# CCE_Simonduino_01.net
KiCad netlist of a schematic drawn in Altium Designer
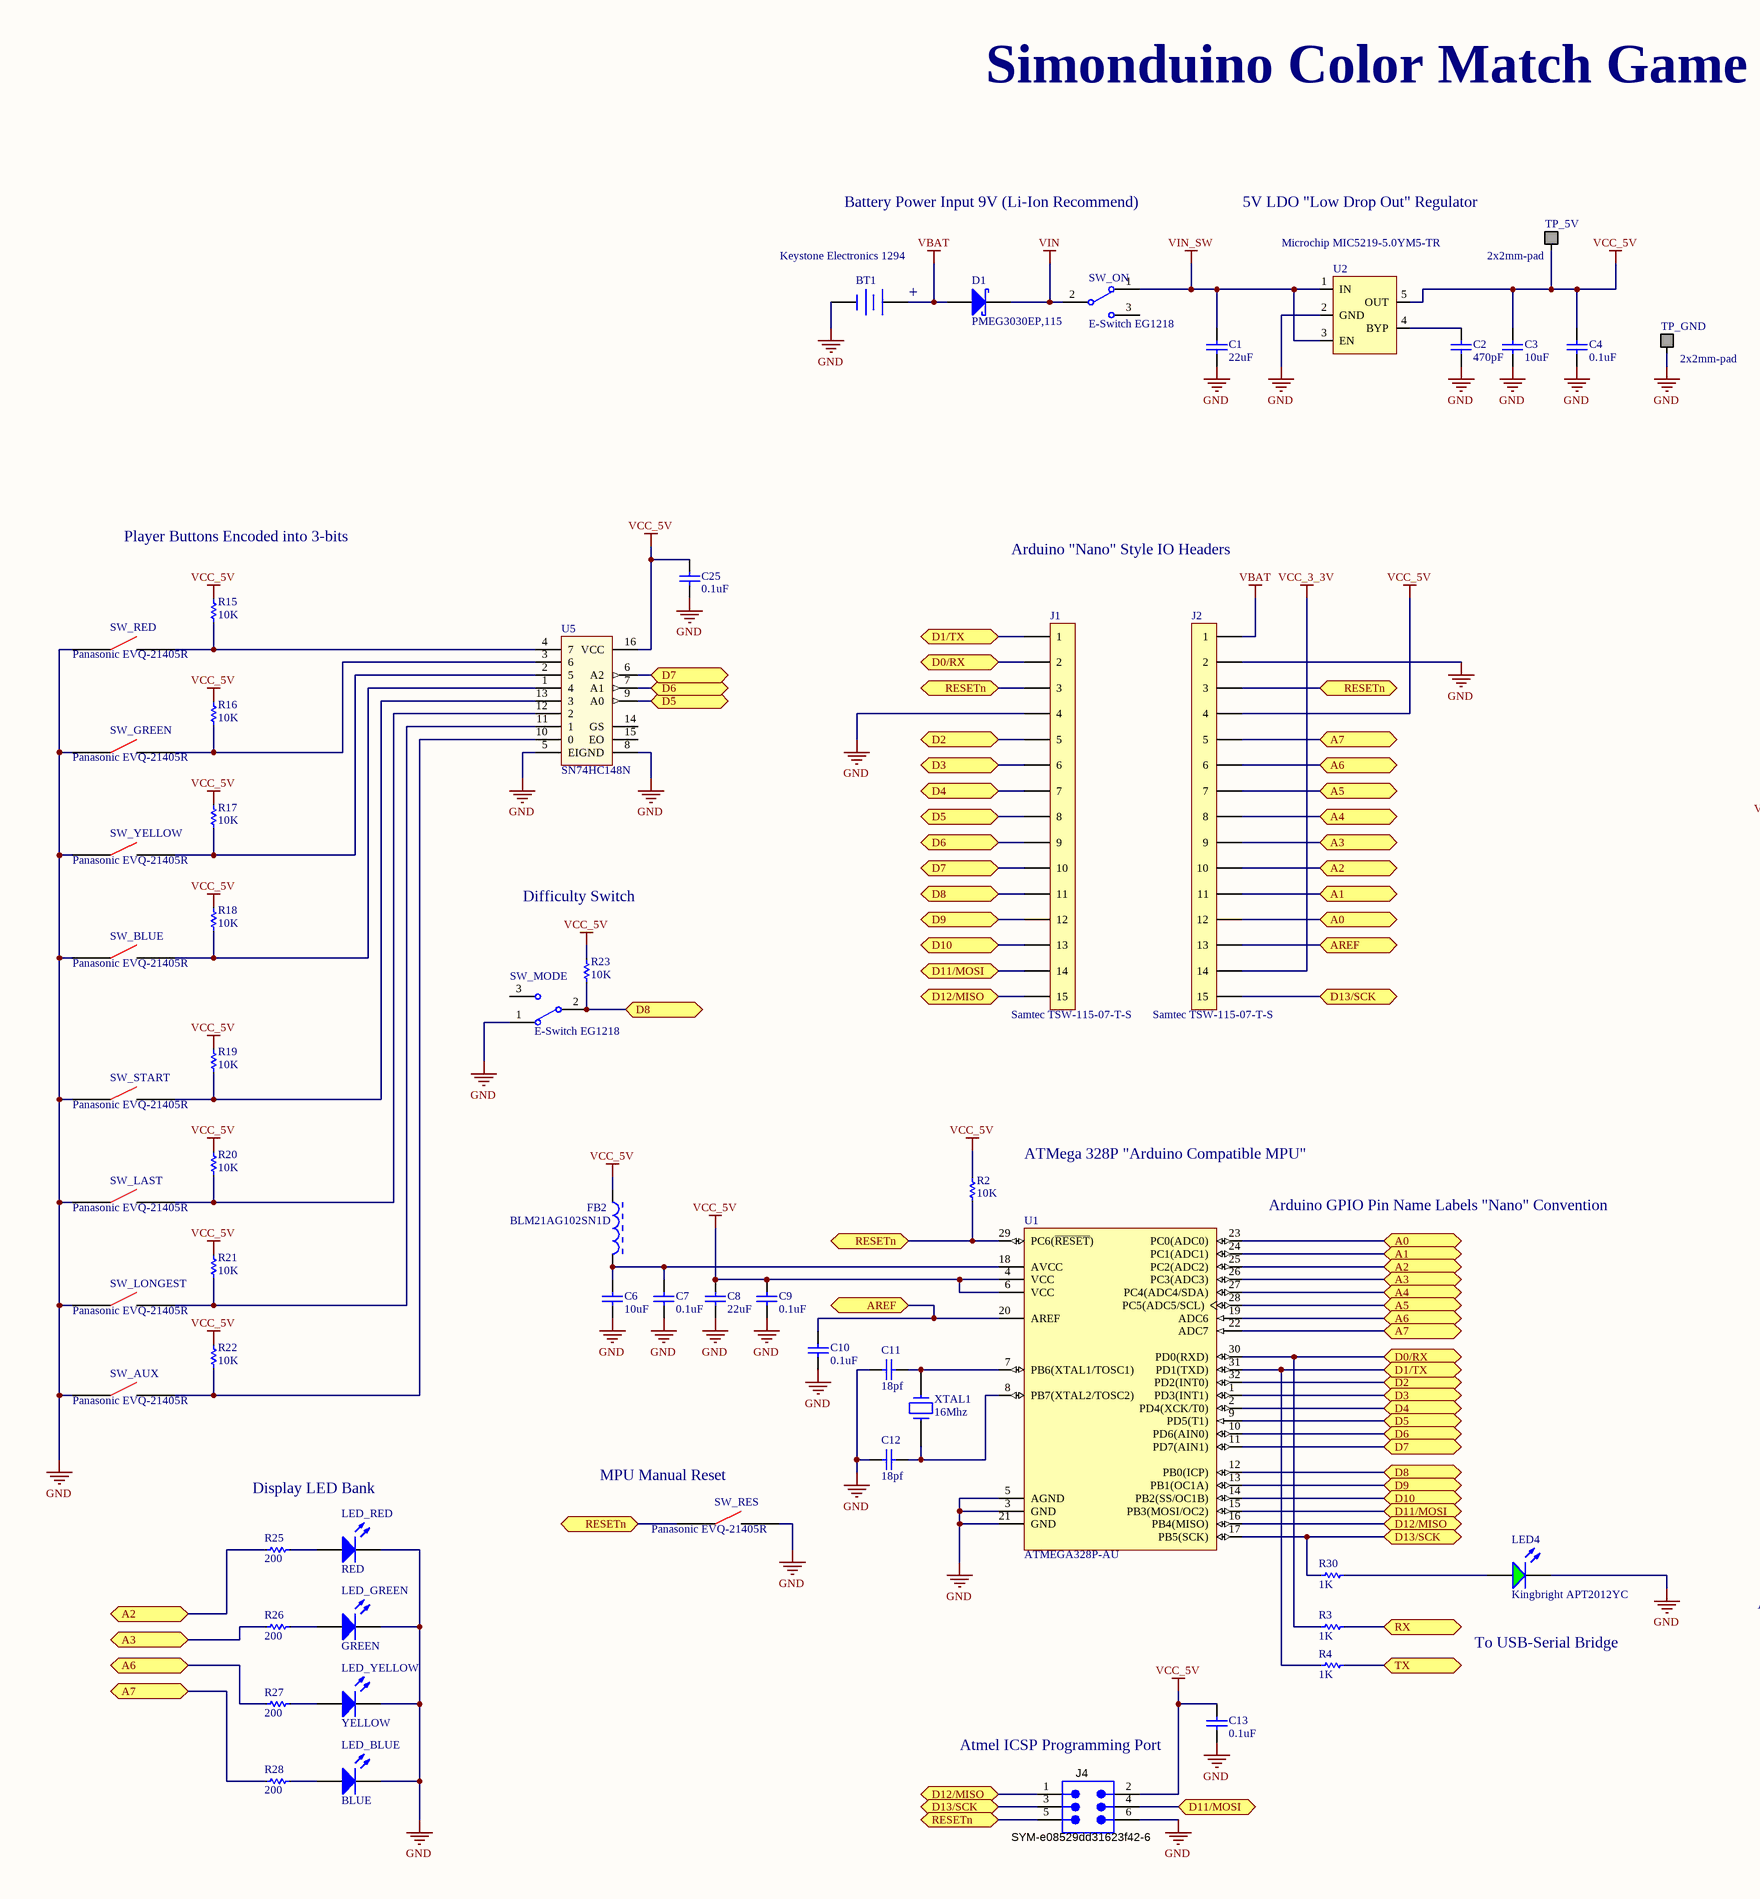
[diagram p0: CCE_Simonduino_01.SchDoc, left]
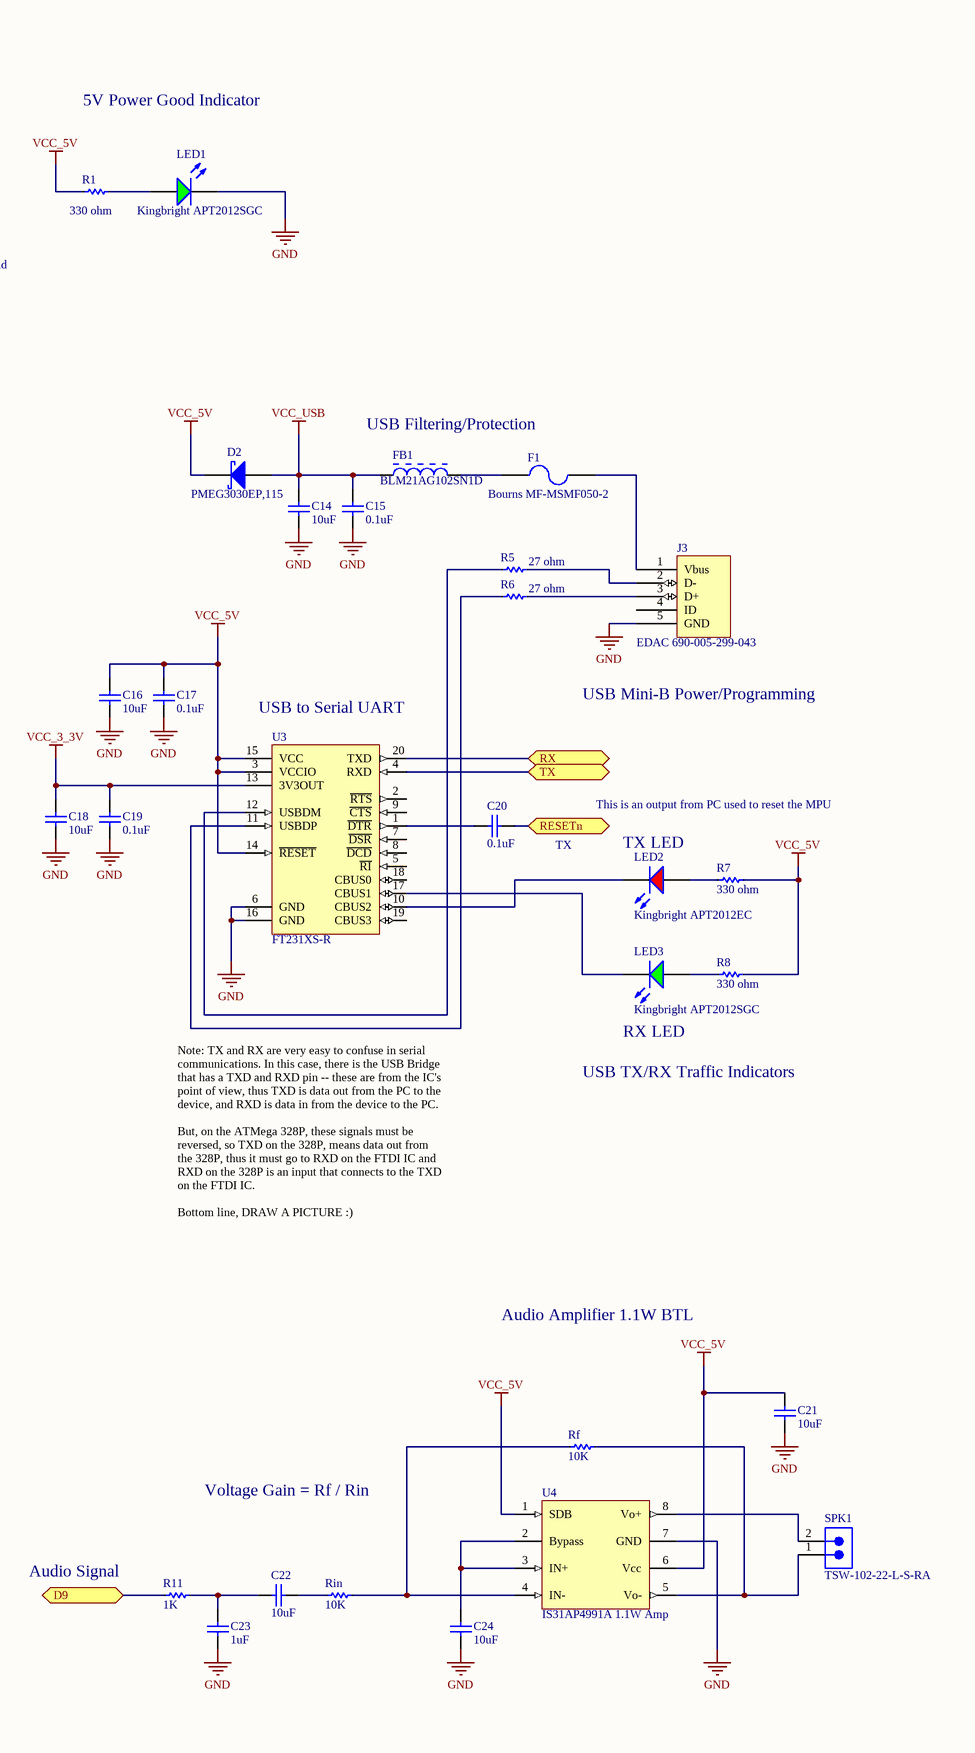
[diagram p1: CCE_Simonduino_01.SchDoc, right]

(export (version "E")
  (design (tool "Eeschema 10.0.6"))
  (components
    (comp (ref "BT1")
      (value "Keystone Electronics 1294")
      (footprint "PCB-3798-1")
      (description "HOLDER BATT 9V UNIV PLASTIC PC")
      (libsource (lib "Octopart library") (part "SYM-3798-1"))
    )
    (comp (ref "C1")
      (value "22uF")
      (footprint "RLP133A")
      (description "Generic Multilayer Ceramic Capacitor SMD 0805 (2012)")
      (libsource (lib "Octopart library") (part "SYM-3c98f6df3913e35f-5"))
    )
    (comp (ref "C2")
      (value "470pF")
      (footprint "RLP133A")
      (description "Generic Multilayer Ceramic Capacitor SMD 0805 (2012)")
      (libsource (lib "CommunityVault") (part "SYM-3c98f6df3913e35f-5"))
    )
    (comp (ref "C3")
      (value "10uF")
      (footprint "RLP133A")
      (description "Generic Multilayer Ceramic Capacitor SMD 0805 (2012)")
      (libsource (lib "Octopart library") (part "SYM-3c98f6df3913e35f-5"))
    )
    (comp (ref "C4")
      (value "0.1uF")
      (footprint "RLP133A")
      (description "Generic Multilayer Ceramic Capacitor SMD 0805 (2012)")
      (libsource (lib "Octopart library") (part "SYM-3c98f6df3913e35f-5"))
    )
    (comp (ref "C6")
      (value "10uF")
      (footprint "RLP133A")
      (description "Generic Multilayer Ceramic Capacitor SMD 0805 (2012)")
      (libsource (lib "Octopart library") (part "SYM-3c98f6df3913e35f-5"))
    )
    (comp (ref "C7")
      (value "0.1uF")
      (footprint "RLP133A")
      (description "Generic Multilayer Ceramic Capacitor SMD 0805 (2012)")
      (libsource (lib "Octopart library") (part "SYM-3c98f6df3913e35f-5"))
    )
    (comp (ref "C8")
      (value "22uF")
      (footprint "RLP133A")
      (description "Generic Multilayer Ceramic Capacitor SMD 0805 (2012)")
      (libsource (lib "Octopart library") (part "SYM-3c98f6df3913e35f-5"))
    )
    (comp (ref "C9")
      (value "0.1uF")
      (footprint "RLP133A")
      (description "Generic Multilayer Ceramic Capacitor SMD 0805 (2012)")
      (libsource (lib "Octopart library") (part "SYM-3c98f6df3913e35f-5"))
    )
    (comp (ref "C10")
      (value "0.1uF")
      (footprint "RLP133A")
      (description "Generic Multilayer Ceramic Capacitor SMD 0805 (2012)")
      (libsource (lib "Octopart library") (part "SYM-3c98f6df3913e35f-5"))
    )
    (comp (ref "C11")
      (value "18pf")
      (footprint "RLP133A")
      (description "Generic Multilayer Ceramic Capacitor SMD 0805 (2012)")
      (libsource (lib "Octopart library") (part "SYM-3c98f6df3913e35f-5"))
    )
    (comp (ref "C12")
      (value "18pf")
      (footprint "RLP133A")
      (description "Generic Multilayer Ceramic Capacitor SMD 0805 (2012)")
      (libsource (lib "Octopart library") (part "SYM-3c98f6df3913e35f-5"))
    )
    (comp (ref "C13")
      (value "0.1uF")
      (footprint "RLP133A")
      (description "Generic Multilayer Ceramic Capacitor SMD 0805 (2012)")
      (libsource (lib "Octopart library") (part "SYM-3c98f6df3913e35f-5"))
    )
    (comp (ref "C14")
      (value "10uF")
      (footprint "RLP133A")
      (description "Generic Multilayer Ceramic Capacitor SMD 0805 (2012)")
      (libsource (lib "Octopart library") (part "SYM-3c98f6df3913e35f-5"))
    )
    (comp (ref "C15")
      (value "0.1uF")
      (footprint "RLP133A")
      (description "Generic Multilayer Ceramic Capacitor SMD 0805 (2012)")
      (libsource (lib "Octopart library") (part "SYM-3c98f6df3913e35f-5"))
    )
    (comp (ref "C16")
      (value "10uF")
      (footprint "RLP133A")
      (description "Generic Multilayer Ceramic Capacitor SMD 0805 (2012)")
      (libsource (lib "Octopart library") (part "SYM-3c98f6df3913e35f-5"))
    )
    (comp (ref "C17")
      (value "0.1uF")
      (footprint "RLP133A")
      (description "Generic Multilayer Ceramic Capacitor SMD 0805 (2012)")
      (libsource (lib "Octopart library") (part "SYM-3c98f6df3913e35f-5"))
    )
    (comp (ref "C18")
      (value "10uF")
      (footprint "RLP133A")
      (description "Generic Multilayer Ceramic Capacitor SMD 0805 (2012)")
      (libsource (lib "Octopart library") (part "SYM-3c98f6df3913e35f-5"))
    )
    (comp (ref "C19")
      (value "0.1uF")
      (footprint "RLP133A")
      (description "Generic Multilayer Ceramic Capacitor SMD 0805 (2012)")
      (libsource (lib "Octopart library") (part "SYM-3c98f6df3913e35f-5"))
    )
    (comp (ref "C20")
      (value "0.1uF")
      (footprint "RLP133A")
      (description "Generic Multilayer Ceramic Capacitor SMD 0805 (2012)")
      (libsource (lib "Octopart library") (part "SYM-3c98f6df3913e35f-5"))
    )
    (comp (ref "C21")
      (value "10uF")
      (footprint "RLP133A")
      (description "Generic Multilayer Ceramic Capacitor SMD 0805 (2012)")
      (libsource (lib "Octopart library") (part "SYM-3c98f6df3913e35f-5"))
    )
    (comp (ref "C22")
      (value "10uF")
      (footprint "RLP133A")
      (description "Generic Multilayer Ceramic Capacitor SMD 0805 (2012)")
      (libsource (lib "Octopart library") (part "SYM-3c98f6df3913e35f-5"))
    )
    (comp (ref "C23")
      (value "1uF")
      (footprint "RLP133A")
      (description "Generic Multilayer Ceramic Capacitor SMD 0805 (2012)")
      (libsource (lib "Octopart library") (part "SYM-3c98f6df3913e35f-5"))
    )
    (comp (ref "C24")
      (value "10uF")
      (footprint "RLP133A")
      (description "Generic Multilayer Ceramic Capacitor SMD 0805 (2012)")
      (libsource (lib "Octopart library") (part "SYM-3c98f6df3913e35f-5"))
    )
    (comp (ref "C25")
      (value "0.1uF")
      (footprint "RLP133A")
      (description "Generic Multilayer Ceramic Capacitor SMD 0805 (2012)")
      (libsource (lib "Octopart library") (part "SYM-3c98f6df3913e35f-5"))
    )
    (comp (ref "D1")
      (value "PMEG3030EP,115")
      (footprint "PCB-ylvpw7uho1dkst7hexks-1")
      (description "PMEG3030EP 3 A 30 Vrrm SMT MEGA Schottky Barrier Rectifier - SOD-128F")
      (libsource (lib "Octopart library") (part "SYM-93505b4aaf424c97-1"))
    )
    (comp (ref "D2")
      (value "PMEG3030EP,115")
      (footprint "PCB-ylvpw7uho1dkst7hexks-1")
      (description "PMEG3030EP 3 A 30 Vrrm SMT MEGA Schottky Barrier Rectifier - SOD-128F")
      (libsource (lib "Octopart library") (part "SYM-93505b4aaf424c97-1"))
    )
    (comp (ref "F1")
      (value "Bourns MF-MSMF050-2")
      (footprint "L1812")
      (description "PTC RESETTABLE .50A 15V 1812")
      (libsource (lib "Octopart library") (part "BOUR-MF-MSMF050-2"))
    )
    (comp (ref "FB1")
      (value "BLM21AG102SN1D")
      (footprint "MURA-BLM21-H1-CHIP-2_V")
      (libsource (lib "Octopart library") (part "MURA-FB-2"))
    )
    (comp (ref "FB2")
      (value "BLM21AG102SN1D")
      (footprint "MURA-BLM21-H1-CHIP-2_V")
      (libsource (lib "Octopart library") (part "MURA-FB-2"))
    )
    (comp (ref "J1")
      (value "Samtec TSW-115-07-T-S")
      (footprint "PCB-ss9uik38su1ryg1jck95-1")
      (description "Conn Unshrouded Header HDR 15 POS 2.54mm Solder ST Thru-Hole Automotive Bulk")
      (libsource (lib "") (part "SYM-3393fa9d3e8bec54-1_1"))
    )
    (comp (ref "J2")
      (value "Samtec TSW-115-07-T-S")
      (footprint "PCB-ss9uik38su1ryg1jck95-1")
      (description "Conn Unshrouded Header HDR 15 POS 2.54mm Solder ST Thru-Hole Automotive Bulk")
      (libsource (lib "Octopart library") (part "SYM-3393fa9d3e8bec54-1"))
    )
    (comp (ref "J3")
      (value "EDAC 690-005-299-043")
      (footprint "PCB-0dqtvzwtjwndkeioqta0-1")
      (description "5 Pin Right Angle Surface Mount Mini USB Type B")
      (libsource (lib "CommunityVault") (part "SYM-f10139da97e32ec6-1"))
    )
    (comp (ref "J4")
      (value "SYM-e08529dd31623f42-6")
      (footprint "PCB-2h1t0rpz2tx2wsc79kkt-1")
      (description "2.54mm (0.1\") Pitch DIL Vertical PC Tail Pin Header, 6.1mm mating pin height, tin, 3+3 contacts")
      (fields (field (name "MANUFACTURER PART NUMBER") "M20-9980346"))
      (libsource (lib "Octopart library") (part "SYM-e08529dd31623f42-6"))
    )
    (comp (ref "LED1")
      (value "Kingbright APT2012SGC")
      (footprint "CHIPLED_0805_NOOUTLINE")
      (description "LED 2X1.2MM 568NM GN WTR CLR SMD")
      (libsource (lib "Octopart library") (part "LED_GREEN_AC"))
    )
    (comp (ref "LED2")
      (value "Kingbright APT2012EC")
      (footprint "CHIPLED_0805_NOOUTLINE")
      (description "LED 2X1.2MM 625NM RD WTR CLR SMD")
      (libsource (lib "Octopart library") (part "LED_RED_AC"))
    )
    (comp (ref "LED3")
      (value "Kingbright APT2012SGC")
      (footprint "CHIPLED_0805_NOOUTLINE")
      (description "LED 2X1.2MM 568NM GN WTR CLR SMD")
      (libsource (lib "Octopart library") (part "LED_GREEN_AC"))
    )
    (comp (ref "LED4")
      (value "Kingbright APT2012YC")
      (footprint "CHIPLED_0805_NOOUTLINE")
      (description "LED 2X1.2MM 568NM GN WTR CLR SMD")
      (libsource (lib "CommunityVault") (part "CMP-1546221-2"))
    )
    (comp (ref "LED_BLUE")
      (value "BLUE")
      (footprint "PCB-teu6t62n2bsx7jl1if62-1")
      (description "LED Uni-Color Green 2-Pin T-1 3/4 Bulk")
      (fields
        (field (name "MANUFACTURER PART NUMBER") "C503B-GCN-CY0C0791")
        (field (name "MANUFACTURER") "Cree")
      )
      (libsource (lib "FavoritesLibrary") (part "SYM-92bb5b2eff764d7c-1"))
    )
    (comp (ref "LED_GREEN")
      (value "GREEN")
      (footprint "PCB-teu6t62n2bsx7jl1if62-1")
      (description "LED Uni-Color Green 2-Pin T-1 3/4 Bulk")
      (fields
        (field (name "MANUFACTURER PART NUMBER") "C503B-GCN-CY0C0791")
        (field (name "MANUFACTURER") "Cree")
      )
      (libsource (lib "FavoritesLibrary") (part "SYM-92bb5b2eff764d7c-1"))
    )
    (comp (ref "LED_RED")
      (value "RED")
      (footprint "PCB-teu6t62n2bsx7jl1if62-1")
      (description "LED Uni-Color Green 2-Pin T-1 3/4 Bulk")
      (fields
        (field (name "MANUFACTURER PART NUMBER") "C503B-GCN-CY0C0791")
        (field (name "MANUFACTURER") "Cree")
      )
      (libsource (lib "FavoritesLibrary") (part "SYM-92bb5b2eff764d7c-1"))
    )
    (comp (ref "LED_YELLOW")
      (value "YELLOW")
      (footprint "PCB-teu6t62n2bsx7jl1if62-1")
      (description "LED Uni-Color Green 2-Pin T-1 3/4 Bulk")
      (fields
        (field (name "MANUFACTURER PART NUMBER") "C503B-GCN-CY0C0791")
        (field (name "MANUFACTURER") "Cree")
      )
      (libsource (lib "FavoritesLibrary") (part "SYM-92bb5b2eff764d7c-1"))
    )
    (comp (ref "R1")
      (value "330 ohm")
      (footprint "RESC2013X70X40LL20T20")
      (description "@ RESISTOR,SMT,0805,1K OHM, +/-1%,+-100ppm,THICKFILM(100)")
      (libsource (lib "Octopart library") (part "RES-2"))
    )
    (comp (ref "R2")
      (value "10K")
      (footprint "RESC2013X70X40LL20T20")
      (description "@ RESISTOR,SMT,0805,1K OHM, +/-1%,+-100ppm,THICKFILM(100)")
      (libsource (lib "Octopart library") (part "RES-2"))
    )
    (comp (ref "R3")
      (value "1K")
      (footprint "RESC2013X70X40LL20T20")
      (description "@ RESISTOR,SMT,0805,1K OHM, +/-1%,+-100ppm,THICKFILM(100)")
      (libsource (lib "Octopart library") (part "RES-2"))
    )
    (comp (ref "R4")
      (value "1K")
      (footprint "RESC2013X70X40LL20T20")
      (description "@ RESISTOR,SMT,0805,1K OHM, +/-1%,+-100ppm,THICKFILM(100)")
      (libsource (lib "Octopart library") (part "RES-2"))
    )
    (comp (ref "R5")
      (value "27 ohm")
      (footprint "RESC2013X70X40LL20T20")
      (description "@ RESISTOR,SMT,0805,1K OHM, +/-1%,+-100ppm,THICKFILM(100)")
      (libsource (lib "Octopart library") (part "RES-2"))
    )
    (comp (ref "R6")
      (value "27 ohm")
      (footprint "RESC2013X70X40LL20T20")
      (description "@ RESISTOR,SMT,0805,1K OHM, +/-1%,+-100ppm,THICKFILM(100)")
      (libsource (lib "Octopart library") (part "RES-2"))
    )
    (comp (ref "R7")
      (value "330 ohm")
      (footprint "RESC2013X70X40LL20T20")
      (description "@ RESISTOR,SMT,0805,1K OHM, +/-1%,+-100ppm,THICKFILM(100)")
      (libsource (lib "Octopart library") (part "RES-2"))
    )
    (comp (ref "R8")
      (value "330 ohm")
      (footprint "RESC2013X70X40LL20T20")
      (description "@ RESISTOR,SMT,0805,1K OHM, +/-1%,+-100ppm,THICKFILM(100)")
      (libsource (lib "Octopart library") (part "RES-2"))
    )
    (comp (ref "R11")
      (value "1K")
      (footprint "RESC2013X70X40LL20T20")
      (description "@ RESISTOR,SMT,0805,1K OHM, +/-1%,+-100ppm,THICKFILM(100)")
      (libsource (lib "Octopart library") (part "RES-2"))
    )
    (comp (ref "R15")
      (value "10K")
      (footprint "RESC2013X70X40LL20T20")
      (description "@ RESISTOR,SMT,0805,1K OHM, +/-1%,+-100ppm,THICKFILM(100)")
      (libsource (lib "Octopart library") (part "RES-2"))
    )
    (comp (ref "R16")
      (value "10K")
      (footprint "RESC2013X70X40LL20T20")
      (description "@ RESISTOR,SMT,0805,1K OHM, +/-1%,+-100ppm,THICKFILM(100)")
      (libsource (lib "Octopart library") (part "RES-2"))
    )
    (comp (ref "R17")
      (value "10K")
      (footprint "RESC2013X70X40LL20T20")
      (description "@ RESISTOR,SMT,0805,1K OHM, +/-1%,+-100ppm,THICKFILM(100)")
      (libsource (lib "Octopart library") (part "RES-2"))
    )
    (comp (ref "R18")
      (value "10K")
      (footprint "RESC2013X70X40LL20T20")
      (description "@ RESISTOR,SMT,0805,1K OHM, +/-1%,+-100ppm,THICKFILM(100)")
      (libsource (lib "Octopart library") (part "RES-2"))
    )
    (comp (ref "R19")
      (value "10K")
      (footprint "RESC2013X70X40LL20T20")
      (description "@ RESISTOR,SMT,0805,1K OHM, +/-1%,+-100ppm,THICKFILM(100)")
      (libsource (lib "Octopart library") (part "RES-2"))
    )
    (comp (ref "R20")
      (value "10K")
      (footprint "RESC2013X70X40LL20T20")
      (description "@ RESISTOR,SMT,0805,1K OHM, +/-1%,+-100ppm,THICKFILM(100)")
      (libsource (lib "Octopart library") (part "RES-2"))
    )
    (comp (ref "R21")
      (value "10K")
      (footprint "RESC2013X70X40LL20T20")
      (description "@ RESISTOR,SMT,0805,1K OHM, +/-1%,+-100ppm,THICKFILM(100)")
      (libsource (lib "Octopart library") (part "RES-2"))
    )
    (comp (ref "R22")
      (value "10K")
      (footprint "RESC2013X70X40LL20T20")
      (description "@ RESISTOR,SMT,0805,1K OHM, +/-1%,+-100ppm,THICKFILM(100)")
      (libsource (lib "Octopart library") (part "RES-2"))
    )
    (comp (ref "R23")
      (value "10K")
      (footprint "RESC2013X70X40LL20T20")
      (description "@ RESISTOR,SMT,0805,1K OHM, +/-1%,+-100ppm,THICKFILM(100)")
      (libsource (lib "Octopart library") (part "RES-2"))
    )
    (comp (ref "R25")
      (value "200")
      (footprint "RESC2013X70X40LL20T20")
      (description "@ RESISTOR,SMT,0805,1K OHM, +/-1%,+-100ppm,THICKFILM(100)")
      (libsource (lib "Octopart library") (part "RES-2"))
    )
    (comp (ref "R26")
      (value "200")
      (footprint "RESC2013X70X40LL20T20")
      (description "@ RESISTOR,SMT,0805,1K OHM, +/-1%,+-100ppm,THICKFILM(100)")
      (libsource (lib "Octopart library") (part "RES-2"))
    )
    (comp (ref "R27")
      (value "200")
      (footprint "RESC2013X70X40LL20T20")
      (description "@ RESISTOR,SMT,0805,1K OHM, +/-1%,+-100ppm,THICKFILM(100)")
      (libsource (lib "Octopart library") (part "RES-2"))
    )
    (comp (ref "R28")
      (value "200")
      (footprint "RESC2013X70X40LL20T20")
      (description "@ RESISTOR,SMT,0805,1K OHM, +/-1%,+-100ppm,THICKFILM(100)")
      (libsource (lib "Octopart library") (part "RES-2"))
    )
    (comp (ref "R30")
      (value "1K")
      (footprint "RESC2013X70X40LL20T20")
      (description "@ RESISTOR,SMT,0805,1K OHM, +/-1%,+-100ppm,THICKFILM(100)")
      (libsource (lib "Octopart library") (part "RES-2"))
    )
    (comp (ref "Rf")
      (value "10K")
      (footprint "RESC2013X70X40LL20T20")
      (description "@ RESISTOR,SMT,0805,1K OHM, +/-1%,+-100ppm,THICKFILM(100)")
      (libsource (lib "Octopart library") (part "RES-2"))
    )
    (comp (ref "Rin")
      (value "10K")
      (footprint "RESC2013X70X40LL20T20")
      (description "@ RESISTOR,SMT,0805,1K OHM, +/-1%,+-100ppm,THICKFILM(100)")
      (libsource (lib "Octopart library") (part "RES-2"))
    )
    (comp (ref "SPK1")
      (value "TSW-102-22-L-S-RA")
      (footprint "SMTC-TSW-102-22-X-S-RA")
      (libsource (lib "Octopart library") (part "SMTC-TSW-102-X-X-S-X"))
    )
    (comp (ref "SW_AUX")
      (value "Panasonic EVQ-21405R")
      (footprint "PCB-je10m8m3eogq13l465bo-1")
      (description "Switch Tactile N.O. SPST Round Button PC Pins 0.02A 15VDC 1.3N Thru-Hole Radial T/R")
      (fields
        (field (name "ELEMENT14 PART NO.") "2281982")
        (field (name "MANUFACTURER PART NUMBER") "EVQ-21405R")
      )
      (libsource (lib "FavoritesLibrary") (part "SYM-2fe5e5be239cf022-1"))
    )
    (comp (ref "SW_BLUE")
      (value "Panasonic EVQ-21405R")
      (footprint "PCB-je10m8m3eogq13l465bo-1")
      (description "Switch Tactile N.O. SPST Round Button PC Pins 0.02A 15VDC 1.3N Thru-Hole Radial T/R")
      (fields
        (field (name "ELEMENT14 PART NO.") "2281982")
        (field (name "MANUFACTURER PART NUMBER") "EVQ-21405R")
      )
      (libsource (lib "FavoritesLibrary") (part "SYM-2fe5e5be239cf022-1"))
    )
    (comp (ref "SW_GREEN")
      (value "Panasonic EVQ-21405R")
      (footprint "PCB-je10m8m3eogq13l465bo-1")
      (description "Switch Tactile N.O. SPST Round Button PC Pins 0.02A 15VDC 1.3N Thru-Hole Radial T/R")
      (fields
        (field (name "ELEMENT14 PART NO.") "2281982")
        (field (name "MANUFACTURER PART NUMBER") "EVQ-21405R")
      )
      (libsource (lib "FavoritesLibrary") (part "SYM-2fe5e5be239cf022-1"))
    )
    (comp (ref "SW_LAST")
      (value "Panasonic EVQ-21405R")
      (footprint "PCB-je10m8m3eogq13l465bo-1")
      (description "Switch Tactile N.O. SPST Round Button PC Pins 0.02A 15VDC 1.3N Thru-Hole Radial T/R")
      (fields
        (field (name "ELEMENT14 PART NO.") "2281982")
        (field (name "MANUFACTURER PART NUMBER") "EVQ-21405R")
      )
      (libsource (lib "FavoritesLibrary") (part "SYM-2fe5e5be239cf022-1"))
    )
    (comp (ref "SW_LONGEST")
      (value "Panasonic EVQ-21405R")
      (footprint "PCB-je10m8m3eogq13l465bo-1")
      (description "Switch Tactile N.O. SPST Round Button PC Pins 0.02A 15VDC 1.3N Thru-Hole Radial T/R")
      (fields
        (field (name "ELEMENT14 PART NO.") "2281982")
        (field (name "MANUFACTURER PART NUMBER") "EVQ-21405R")
      )
      (libsource (lib "FavoritesLibrary") (part "SYM-2fe5e5be239cf022-1"))
    )
    (comp (ref "SW_MODE")
      (value "E-Switch EG1218")
      (footprint "ESWI-EG1218_V")
      (description "Slide Switch, 500 V, -20 to 70 degC, 3-Pin THD, RoHS")
      (fields (field (name "MANUFACTURER PART NUMBER") "EG1218"))
      (libsource (lib "FavoritesLibrary") (part "SW-SPDT-3_B"))
    )
    (comp (ref "SW_ON")
      (value "E-Switch EG1218")
      (footprint "ESWI-EG1218_V")
      (description "Slide Switch, 500 V, -20 to 70 degC, 3-Pin THD, RoHS")
      (fields (field (name "MANUFACTURER PART NUMBER") "EG1218"))
      (libsource (lib "FavoritesLibrary") (part "SW-SPDT-3_B"))
    )
    (comp (ref "SW_RED")
      (value "Panasonic EVQ-21405R")
      (footprint "PCB-je10m8m3eogq13l465bo-1")
      (description "Switch Tactile N.O. SPST Round Button PC Pins 0.02A 15VDC 1.3N Thru-Hole Radial T/R")
      (fields
        (field (name "ELEMENT14 PART NO.") "2281982")
        (field (name "MANUFACTURER PART NUMBER") "EVQ-21405R")
      )
      (libsource (lib "FavoritesLibrary") (part "SYM-2fe5e5be239cf022-1"))
    )
    (comp (ref "SW_RES")
      (value "Panasonic EVQ-21405R")
      (footprint "PCB-je10m8m3eogq13l465bo-1")
      (description "Switch Tactile N.O. SPST Round Button PC Pins 0.02A 15VDC 1.3N Thru-Hole Radial T/R")
      (fields
        (field (name "ELEMENT14 PART NO.") "2281982")
        (field (name "MANUFACTURER PART NUMBER") "EVQ-21405R")
      )
      (libsource (lib "FavoritesLibrary") (part "SYM-2fe5e5be239cf022-1"))
    )
    (comp (ref "SW_START")
      (value "Panasonic EVQ-21405R")
      (footprint "PCB-je10m8m3eogq13l465bo-1")
      (description "Switch Tactile N.O. SPST Round Button PC Pins 0.02A 15VDC 1.3N Thru-Hole Radial T/R")
      (fields
        (field (name "ELEMENT14 PART NO.") "2281982")
        (field (name "MANUFACTURER PART NUMBER") "EVQ-21405R")
      )
      (libsource (lib "FavoritesLibrary") (part "SYM-2fe5e5be239cf022-1"))
    )
    (comp (ref "SW_YELLOW")
      (value "Panasonic EVQ-21405R")
      (footprint "PCB-je10m8m3eogq13l465bo-1")
      (description "Switch Tactile N.O. SPST Round Button PC Pins 0.02A 15VDC 1.3N Thru-Hole Radial T/R")
      (fields
        (field (name "ELEMENT14 PART NO.") "2281982")
        (field (name "MANUFACTURER PART NUMBER") "EVQ-21405R")
      )
      (libsource (lib "FavoritesLibrary") (part "SYM-2fe5e5be239cf022-1"))
    )
    (comp (ref "TP_5V")
      (value "2x2mm-pad")
      (footprint "PCB-iek5qk9ganu4yn12lo6h-1")
      (description "Raychem; SMT Circuit probe pad, 0805, 0R0 RCT")
      (libsource (lib "Octopart library") (part "SYM-da21135b2be305e6-1"))
    )
    (comp (ref "TP_GND")
      (value "2x2mm-pad")
      (footprint "PCB-iek5qk9ganu4yn12lo6h-1")
      (description "Raychem; SMT Circuit probe pad, 0805, 0R0 RCT")
      (libsource (lib "Octopart library") (part "SYM-da21135b2be305e6-1"))
    )
    (comp (ref "U1")
      (value "ATMEGA328P-AU")
      (footprint "TQFP32-08")
      (libsource (lib "Octopart library") (part "ATMEGA328P-AU"))
    )
    (comp (ref "U2")
      (value "Microchip MIC5219-5.0YM5-TR")
      (footprint "PCB-wkjlo8hhy83bmub82728-1")
      (description "MIC5219 Series 500 mA 5 V Fixed Output Surface Mount LDO Regulator - SOT-23-5")
      (fields (field (name "MANUFACTURER PART NUMBER") "MIC5219-5.0YM5-TR"))
      (libsource (lib "CommunityVault") (part "SYM-8be04111fcdb5427-1"))
    )
    (comp (ref "U3")
      (value "FT231XS-R")
      (footprint "SSOP20_L")
      (description "USB Full Speed to Full Handshake UART with USB Charger Detection")
      (libsource (lib "Octopart library") (part "FTDI-FT231XS-20"))
    )
    (comp (ref "U4")
      (value "IS31AP4991A 1.1W Amp")
      (footprint "PCB-9rmbxp4o58shl47xlmib-1")
      (description "Audio Amp Speaker 1-CH Mono 1.4W Class-AB 8-Pin SOP T/R")
      (libsource (lib "Octopart library") (part "SYM-b3f478ed30436c33-1"))
    )
    (comp (ref "U5")
      (value "SN74HC148N")
      (footprint "PCB-humlfp2qb5uk19pmpc47-1")
      (description "8-Line To 3-Line Priority Encoders 16-SOIC -40 to 85")
      (libsource (lib "Octopart library") (part "SYM-21e6e8edbd0afe21-1"))
    )
    (comp (ref "XTAL1")
      (value "16Mhz")
      (footprint "PCB-tw4o7k9ciwtd4bkcirmp-1")
      (description "Crystal 16.0000 MHz")
      (fields (field (name "MANUFACTURER PART NUMBER") "9B-16.000MEEJ-B"))
      (libsource (lib "Octopart library") (part "SYM-9941515555464686-1"))
    )
  )
  (nets
    (net (code "1") (name "/A0") (class "Default")
      (node (ref "J2") (pin "12") (pinfunction "12_12") (pintype "passive"))
      (node (ref "U1") (pin "23") (pinfunction "PC0(ADC0)_23") (pintype "bidirectional"))
    )
    (net (code "2") (name "/A1") (class "Default")
      (node (ref "J2") (pin "11") (pinfunction "11_11") (pintype "passive"))
      (node (ref "U1") (pin "24") (pinfunction "PC1(ADC1)_24") (pintype "bidirectional"))
    )
    (net (code "3") (name "/A2") (class "Default")
      (node (ref "J2") (pin "10") (pinfunction "10_10") (pintype "passive"))
      (node (ref "R25") (pin "1") (pinfunction "1_1") (pintype "passive"))
      (node (ref "U1") (pin "25") (pinfunction "PC2(ADC2)_25") (pintype "bidirectional"))
    )
    (net (code "4") (name "/A3") (class "Default")
      (node (ref "J2") (pin "9") (pinfunction "9_9") (pintype "passive"))
      (node (ref "R26") (pin "1") (pinfunction "1_1") (pintype "passive"))
      (node (ref "U1") (pin "26") (pinfunction "PC3(ADC3)_26") (pintype "bidirectional"))
    )
    (net (code "5") (name "/A4") (class "Default")
      (node (ref "J2") (pin "8") (pinfunction "8_8") (pintype "passive"))
      (node (ref "U1") (pin "27") (pinfunction "PC4(ADC4/SDA)_27") (pintype "bidirectional"))
    )
    (net (code "6") (name "/A5") (class "Default")
      (node (ref "J2") (pin "7") (pinfunction "7_7") (pintype "passive"))
      (node (ref "U1") (pin "28") (pinfunction "PC5(ADC5/SCL)_28") (pintype "bidirectional"))
    )
    (net (code "7") (name "/A6") (class "Default")
      (node (ref "J2") (pin "6") (pinfunction "6_6") (pintype "passive"))
      (node (ref "R27") (pin "1") (pinfunction "1_1") (pintype "passive"))
      (node (ref "U1") (pin "19") (pinfunction "ADC6_19") (pintype "input"))
    )
    (net (code "8") (name "/A7") (class "Default")
      (node (ref "J2") (pin "5") (pinfunction "5_5") (pintype "passive"))
      (node (ref "R28") (pin "1") (pinfunction "1_1") (pintype "passive"))
      (node (ref "U1") (pin "22") (pinfunction "ADC7_22") (pintype "input"))
    )
    (net (code "9") (name "/AREF") (class "Default")
      (node (ref "C10") (pin "1") (pinfunction "1_1") (pintype "passive"))
      (node (ref "J2") (pin "13") (pinfunction "13_13") (pintype "passive"))
      (node (ref "U1") (pin "20") (pinfunction "AREF_20") (pintype "passive"))
    )
    (net (code "10") (name "/D0{slash}RX") (class "Default")
      (node (ref "J1") (pin "2") (pinfunction "2_2") (pintype "passive"))
      (node (ref "R3") (pin "1") (pinfunction "1_1") (pintype "passive"))
      (node (ref "U1") (pin "30") (pinfunction "PD0(RXD)_30") (pintype "bidirectional"))
    )
    (net (code "11") (name "/D1{slash}TX") (class "Default")
      (node (ref "J1") (pin "1") (pinfunction "1_1") (pintype "passive"))
      (node (ref "R4") (pin "1") (pinfunction "1_1") (pintype "passive"))
      (node (ref "U1") (pin "31") (pinfunction "PD1(TXD)_31") (pintype "bidirectional"))
    )
    (net (code "12") (name "/D2") (class "Default")
      (node (ref "J1") (pin "5") (pinfunction "5_5") (pintype "passive"))
      (node (ref "U1") (pin "32") (pinfunction "PD2(INT0)_32") (pintype "bidirectional"))
    )
    (net (code "13") (name "/D3") (class "Default")
      (node (ref "J1") (pin "6") (pinfunction "6_6") (pintype "passive"))
      (node (ref "U1") (pin "1") (pinfunction "PD3(INT1)_1") (pintype "bidirectional"))
    )
    (net (code "14") (name "/D4") (class "Default")
      (node (ref "J1") (pin "7") (pinfunction "7_7") (pintype "passive"))
      (node (ref "U1") (pin "2") (pinfunction "PD4(XCK/T0)_2") (pintype "bidirectional"))
    )
    (net (code "15") (name "/D5") (class "Default")
      (node (ref "J1") (pin "8") (pinfunction "8_8") (pintype "passive"))
      (node (ref "U1") (pin "9") (pinfunction "PD5(T1)_9") (pintype "input"))
      (node (ref "U5") (pin "9") (pinfunction "A0_9") (pintype "output"))
    )
    (net (code "16") (name "/D6") (class "Default")
      (node (ref "J1") (pin "9") (pinfunction "9_9") (pintype "passive"))
      (node (ref "U1") (pin "10") (pinfunction "PD6(AIN0)_10") (pintype "bidirectional"))
      (node (ref "U5") (pin "7") (pinfunction "A1_7") (pintype "output"))
    )
    (net (code "17") (name "/D7") (class "Default")
      (node (ref "J1") (pin "10") (pinfunction "10_10") (pintype "passive"))
      (node (ref "U1") (pin "11") (pinfunction "PD7(AIN1)_11") (pintype "bidirectional"))
      (node (ref "U5") (pin "6") (pinfunction "A2_6") (pintype "output"))
    )
    (net (code "18") (name "/D8") (class "Default")
      (node (ref "J1") (pin "11") (pinfunction "11_11") (pintype "passive"))
      (node (ref "R23") (pin "2") (pinfunction "2_2") (pintype "passive"))
      (node (ref "SW_MODE") (pin "2") (pinfunction "COM_2") (pintype "passive"))
      (node (ref "U1") (pin "12") (pinfunction "PB0(ICP)_12") (pintype "bidirectional"))
    )
    (net (code "19") (name "/D9") (class "Default")
      (node (ref "J1") (pin "12") (pinfunction "12_12") (pintype "passive"))
      (node (ref "R11") (pin "2") (pinfunction "2_2") (pintype "passive"))
      (node (ref "U1") (pin "13") (pinfunction "PB1(OC1A)_13") (pintype "bidirectional"))
    )
    (net (code "20") (name "/D10") (class "Default")
      (node (ref "J1") (pin "13") (pinfunction "13_13") (pintype "passive"))
      (node (ref "U1") (pin "14") (pinfunction "PB2(SS/OC1B)_14") (pintype "bidirectional"))
    )
    (net (code "21") (name "/D11{slash}MOSI") (class "Default")
      (node (ref "J1") (pin "14") (pinfunction "14_14") (pintype "passive"))
      (node (ref "J4") (pin "4") (pinfunction "4_4") (pintype "passive"))
      (node (ref "U1") (pin "15") (pinfunction "PB3(MOSI/OC2)_15") (pintype "bidirectional"))
    )
    (net (code "22") (name "/D12{slash}MISO") (class "Default")
      (node (ref "J1") (pin "15") (pinfunction "15_15") (pintype "passive"))
      (node (ref "J4") (pin "1") (pinfunction "1_1") (pintype "passive"))
      (node (ref "U1") (pin "16") (pinfunction "PB4(MISO)_16") (pintype "bidirectional"))
    )
    (net (code "23") (name "/D13{slash}SCK") (class "Default")
      (node (ref "J2") (pin "15") (pinfunction "15_15") (pintype "passive"))
      (node (ref "J4") (pin "3") (pinfunction "3_3") (pintype "passive"))
      (node (ref "R30") (pin "1") (pinfunction "1_1") (pintype "passive"))
      (node (ref "U1") (pin "17") (pinfunction "PB5(SCK)_17") (pintype "bidirectional"))
    )
    (net (code "24") (name "/RESETn") (class "Default")
      (node (ref "C20") (pin "1") (pinfunction "1_1") (pintype "passive"))
      (node (ref "J1") (pin "3") (pinfunction "3_3") (pintype "passive"))
      (node (ref "J2") (pin "3") (pinfunction "3_3") (pintype "passive"))
      (node (ref "J4") (pin "5") (pinfunction "5_5") (pintype "passive"))
      (node (ref "R2") (pin "1") (pinfunction "1_1") (pintype "passive"))
      (node (ref "SW_RES") (pin "1") (pinfunction "1_1") (pintype "passive"))
      (node (ref "U1") (pin "29") (pinfunction "PC6(~{RESET})_29") (pintype "bidirectional"))
    )
    (net (code "25") (name "/RX") (class "Default")
      (node (ref "R3") (pin "2") (pinfunction "2_2") (pintype "passive"))
      (node (ref "U3") (pin "20") (pinfunction "TXD_20") (pintype "output"))
    )
    (net (code "26") (name "/TX") (class "Default")
      (node (ref "R4") (pin "2") (pinfunction "2_2") (pintype "passive"))
      (node (ref "U3") (pin "4") (pinfunction "RXD_4") (pintype "input"))
    )
    (net (code "27") (name "GND") (class "Default")
      (node (ref "BT1") (pin "2") (pinfunction "-_2") (pintype "passive"))
      (node (ref "C1") (pin "1") (pinfunction "1_1") (pintype "passive"))
      (node (ref "C10") (pin "2") (pinfunction "2_2") (pintype "passive"))
      (node (ref "C11") (pin "2") (pinfunction "2_2") (pintype "passive"))
      (node (ref "C12") (pin "2") (pinfunction "2_2") (pintype "passive"))
      (node (ref "C13") (pin "2") (pinfunction "2_2") (pintype "passive"))
      (node (ref "C14") (pin "1") (pinfunction "1_1") (pintype "passive"))
      (node (ref "C15") (pin "1") (pinfunction "1_1") (pintype "passive"))
      (node (ref "C16") (pin "1") (pinfunction "1_1") (pintype "passive"))
      (node (ref "C17") (pin "1") (pinfunction "1_1") (pintype "passive"))
      (node (ref "C18") (pin "1") (pinfunction "1_1") (pintype "passive"))
      (node (ref "C19") (pin "1") (pinfunction "1_1") (pintype "passive"))
      (node (ref "C2") (pin "1") (pinfunction "1_1") (pintype "passive"))
      (node (ref "C21") (pin "1") (pinfunction "1_1") (pintype "passive"))
      (node (ref "C23") (pin "2") (pinfunction "2_2") (pintype "passive"))
      (node (ref "C24") (pin "1") (pinfunction "1_1") (pintype "passive"))
      (node (ref "C25") (pin "1") (pinfunction "1_1") (pintype "passive"))
      (node (ref "C3") (pin "1") (pinfunction "1_1") (pintype "passive"))
      (node (ref "C4") (pin "1") (pinfunction "1_1") (pintype "passive"))
      (node (ref "C6") (pin "1") (pinfunction "1_1") (pintype "passive"))
      (node (ref "C7") (pin "1") (pinfunction "1_1") (pintype "passive"))
      (node (ref "C8") (pin "1") (pinfunction "1_1") (pintype "passive"))
      (node (ref "C9") (pin "1") (pinfunction "1_1") (pintype "passive"))
      (node (ref "J1") (pin "4") (pinfunction "4_4") (pintype "passive"))
      (node (ref "J2") (pin "2") (pinfunction "2_2") (pintype "passive"))
      (node (ref "J3") (pin "5") (pinfunction "GND_5") (pintype "power_in"))
      (node (ref "J4") (pin "6") (pinfunction "6_6") (pintype "passive"))
      (node (ref "LED1") (pin "C") (pinfunction "C_C") (pintype "passive"))
      (node (ref "LED4") (pin "C") (pinfunction "C_C") (pintype "passive"))
      (node (ref "LED_BLUE") (pin "1") (pinfunction "K_1") (pintype "passive"))
      (node (ref "LED_GREEN") (pin "1") (pinfunction "K_1") (pintype "passive"))
      (node (ref "LED_RED") (pin "1") (pinfunction "K_1") (pintype "passive"))
      (node (ref "LED_YELLOW") (pin "1") (pinfunction "K_1") (pintype "passive"))
      (node (ref "SW_AUX") (pin "1") (pinfunction "1_1") (pintype "passive"))
      (node (ref "SW_BLUE") (pin "1") (pinfunction "1_1") (pintype "passive"))
      (node (ref "SW_GREEN") (pin "1") (pinfunction "1_1") (pintype "passive"))
      (node (ref "SW_LAST") (pin "1") (pinfunction "1_1") (pintype "passive"))
      (node (ref "SW_LONGEST") (pin "1") (pinfunction "1_1") (pintype "passive"))
      (node (ref "SW_MODE") (pin "1") (pinfunction "1_1") (pintype "passive"))
      (node (ref "SW_RED") (pin "1") (pinfunction "1_1") (pintype "passive"))
      (node (ref "SW_RES") (pin "2") (pinfunction "2_2") (pintype "passive"))
      (node (ref "SW_START") (pin "1") (pinfunction "1_1") (pintype "passive"))
      (node (ref "SW_YELLOW") (pin "1") (pinfunction "1_1") (pintype "passive"))
      (node (ref "TP_GND") (pin "1") (pinfunction "1_1") (pintype "passive"))
      (node (ref "U1") (pin "21") (pinfunction "GND_21") (pintype "power_in"))
      (node (ref "U1") (pin "3") (pinfunction "GND_3") (pintype "power_in"))
      (node (ref "U1") (pin "5") (pinfunction "AGND_5") (pintype "power_in"))
      (node (ref "U2") (pin "2") (pinfunction "GND_2") (pintype "passive"))
      (node (ref "U3") (pin "16") (pinfunction "GND_16") (pintype "power_in"))
      (node (ref "U3") (pin "6") (pinfunction "GND_6") (pintype "power_in"))
      (node (ref "U4") (pin "7") (pinfunction "GND_7") (pintype "power_in"))
      (node (ref "U5") (pin "5") (pinfunction "EI_5") (pintype "passive"))
      (node (ref "U5") (pin "8") (pinfunction "GND_8") (pintype "power_in"))
    )
    (net (code "28") (name "Net-(C22-Pad1)") (class "Default")
      (node (ref "C22") (pin "1") (pinfunction "1_1") (pintype "passive"))
      (node (ref "Rin") (pin "1") (pinfunction "1_1") (pintype "passive"))
    )
    (net (code "29") (name "Net-(C22-Pad2)") (class "Default")
      (node (ref "C22") (pin "2") (pinfunction "2_2") (pintype "passive"))
      (node (ref "C23") (pin "1") (pinfunction "1_1") (pintype "passive"))
      (node (ref "R11") (pin "1") (pinfunction "1_1") (pintype "passive"))
    )
    (net (code "30") (name "Net-(F1-Pad1)") (class "Default")
      (node (ref "F1") (pin "1") (pinfunction "1_1") (pintype "passive"))
      (node (ref "FB1") (pin "2") (pinfunction "2_2") (pintype "passive"))
    )
    (net (code "31") (name "Net-(J3-D+)") (class "Default")
      (node (ref "J3") (pin "3") (pinfunction "D+_3") (pintype "bidirectional"))
      (node (ref "R6") (pin "2") (pinfunction "2_2") (pintype "passive"))
    )
    (net (code "32") (name "Net-(J3-D-)") (class "Default")
      (node (ref "J3") (pin "2") (pinfunction "D-_2") (pintype "bidirectional"))
      (node (ref "R5") (pin "2") (pinfunction "2_2") (pintype "passive"))
    )
    (net (code "33") (name "Net-(J3-Vbus)") (class "Default")
      (node (ref "F1") (pin "2") (pinfunction "2_2") (pintype "passive"))
      (node (ref "J3") (pin "1") (pinfunction "Vbus_1") (pintype "power_in"))
    )
    (net (code "34") (name "Net-(LED1-PadA)") (class "Default")
      (node (ref "LED1") (pin "A") (pinfunction "A_A") (pintype "passive"))
      (node (ref "R1") (pin "2") (pinfunction "2_2") (pintype "passive"))
    )
    (net (code "35") (name "Net-(LED2-PadA)") (class "Default")
      (node (ref "LED2") (pin "A") (pinfunction "A_A") (pintype "passive"))
      (node (ref "R7") (pin "2") (pinfunction "2_2") (pintype "passive"))
    )
    (net (code "36") (name "Net-(LED3-PadA)") (class "Default")
      (node (ref "LED3") (pin "A") (pinfunction "A_A") (pintype "passive"))
      (node (ref "R8") (pin "2") (pinfunction "2_2") (pintype "passive"))
    )
    (net (code "37") (name "Net-(LED4-PadA)") (class "Default")
      (node (ref "LED4") (pin "A") (pinfunction "A_A") (pintype "passive"))
      (node (ref "R30") (pin "2") (pinfunction "2_2") (pintype "passive"))
    )
    (net (code "38") (name "Net-(LED_BLUE-A)") (class "Default")
      (node (ref "LED_BLUE") (pin "2") (pinfunction "A_2") (pintype "passive"))
      (node (ref "R28") (pin "2") (pinfunction "2_2") (pintype "passive"))
    )
    (net (code "39") (name "Net-(LED_GREEN-A)") (class "Default")
      (node (ref "LED_GREEN") (pin "2") (pinfunction "A_2") (pintype "passive"))
      (node (ref "R26") (pin "2") (pinfunction "2_2") (pintype "passive"))
    )
    (net (code "40") (name "Net-(LED_RED-A)") (class "Default")
      (node (ref "LED_RED") (pin "2") (pinfunction "A_2") (pintype "passive"))
      (node (ref "R25") (pin "2") (pinfunction "2_2") (pintype "passive"))
    )
    (net (code "41") (name "Net-(LED_YELLOW-A)") (class "Default")
      (node (ref "LED_YELLOW") (pin "2") (pinfunction "A_2") (pintype "passive"))
      (node (ref "R27") (pin "2") (pinfunction "2_2") (pintype "passive"))
    )
    (net (code "42") (name "Net-(U1-AVCC)") (class "Default")
      (node (ref "C6") (pin "2") (pinfunction "2_2") (pintype "passive"))
      (node (ref "C7") (pin "2") (pinfunction "2_2") (pintype "passive"))
      (node (ref "FB2") (pin "2") (pinfunction "2_2") (pintype "passive"))
      (node (ref "U1") (pin "18") (pinfunction "AVCC_18") (pintype "power_in"))
    )
    (net (code "43") (name "Net-(U1-PB6(XTAL1{slash}TOSC1))") (class "Default")
      (node (ref "C11") (pin "1") (pinfunction "1_1") (pintype "passive"))
      (node (ref "U1") (pin "7") (pinfunction "PB6(XTAL1/TOSC1)_7") (pintype "bidirectional"))
      (node (ref "XTAL1") (pin "2") (pinfunction "2_2") (pintype "passive"))
    )
    (net (code "44") (name "Net-(U1-PB7(XTAL2{slash}TOSC2))") (class "Default")
      (node (ref "C12") (pin "1") (pinfunction "1_1") (pintype "passive"))
      (node (ref "U1") (pin "8") (pinfunction "PB7(XTAL2/TOSC2)_8") (pintype "bidirectional"))
      (node (ref "XTAL1") (pin "1") (pinfunction "1_1") (pintype "passive"))
    )
    (net (code "45") (name "Net-(U2-BYP)") (class "Default")
      (node (ref "C2") (pin "2") (pinfunction "2_2") (pintype "passive"))
      (node (ref "U2") (pin "4") (pinfunction "BYP_4") (pintype "passive"))
    )
    (net (code "46") (name "Net-(U3-CBUS1)") (class "Default")
      (node (ref "LED3") (pin "C") (pinfunction "C_C") (pintype "passive"))
      (node (ref "U3") (pin "17") (pinfunction "CBUS1_17") (pintype "bidirectional"))
    )
    (net (code "47") (name "Net-(U3-CBUS2)") (class "Default")
      (node (ref "LED2") (pin "C") (pinfunction "C_C") (pintype "passive"))
      (node (ref "U3") (pin "10") (pinfunction "CBUS2_10") (pintype "bidirectional"))
    )
    (net (code "48") (name "Net-(U3-USBDM)") (class "Default")
      (node (ref "R5") (pin "1") (pinfunction "1_1") (pintype "passive"))
      (node (ref "U3") (pin "12") (pinfunction "USBDM_12") (pintype "input"))
    )
    (net (code "49") (name "Net-(U3-USBDP)") (class "Default")
      (node (ref "R6") (pin "1") (pinfunction "1_1") (pintype "passive"))
      (node (ref "U3") (pin "11") (pinfunction "USBDP_11") (pintype "input"))
    )
    (net (code "50") (name "Net-(U3-~{DTR})") (class "Default")
      (node (ref "C20") (pin "2") (pinfunction "2_2") (pintype "passive"))
      (node (ref "U3") (pin "1") (pinfunction "~{DTR}_1") (pintype "output"))
    )
    (net (code "51") (name "Net-(U4-Bypass)") (class "Default")
      (node (ref "C24") (pin "2") (pinfunction "2_2") (pintype "passive"))
      (node (ref "U4") (pin "2") (pinfunction "Bypass_2") (pintype "passive"))
      (node (ref "U4") (pin "3") (pinfunction "IN+_3") (pintype "input"))
    )
    (net (code "52") (name "Net-(U4-IN-)") (class "Default")
      (node (ref "Rf") (pin "1") (pinfunction "1_1") (pintype "passive"))
      (node (ref "Rin") (pin "2") (pinfunction "2_2") (pintype "passive"))
      (node (ref "U4") (pin "4") (pinfunction "IN-_4") (pintype "input"))
    )
    (net (code "53") (name "Net-(U4-Vo+)") (class "Default")
      (node (ref "SPK1") (pin "2") (pinfunction "2_2") (pintype "passive"))
      (node (ref "U4") (pin "8") (pinfunction "Vo+_8") (pintype "output"))
    )
    (net (code "54") (name "Net-(U4-Vo-)") (class "Default")
      (node (ref "Rf") (pin "2") (pinfunction "2_2") (pintype "passive"))
      (node (ref "SPK1") (pin "1") (pinfunction "1_1") (pintype "passive"))
      (node (ref "U4") (pin "5") (pinfunction "Vo-_5") (pintype "output"))
    )
    (net (code "55") (name "Net-(U5-0)") (class "Default")
      (node (ref "R22") (pin "2") (pinfunction "2_2") (pintype "passive"))
      (node (ref "SW_AUX") (pin "2") (pinfunction "2_2") (pintype "passive"))
      (node (ref "U5") (pin "10") (pinfunction "0_10") (pintype "passive"))
    )
    (net (code "56") (name "Net-(U5-1)") (class "Default")
      (node (ref "R21") (pin "2") (pinfunction "2_2") (pintype "passive"))
      (node (ref "SW_LONGEST") (pin "2") (pinfunction "2_2") (pintype "passive"))
      (node (ref "U5") (pin "11") (pinfunction "1_11") (pintype "passive"))
    )
    (net (code "57") (name "Net-(U5-2)") (class "Default")
      (node (ref "R20") (pin "2") (pinfunction "2_2") (pintype "passive"))
      (node (ref "SW_LAST") (pin "2") (pinfunction "2_2") (pintype "passive"))
      (node (ref "U5") (pin "12") (pinfunction "2_12") (pintype "passive"))
    )
    (net (code "58") (name "Net-(U5-3)") (class "Default")
      (node (ref "R19") (pin "2") (pinfunction "2_2") (pintype "passive"))
      (node (ref "SW_START") (pin "2") (pinfunction "2_2") (pintype "passive"))
      (node (ref "U5") (pin "13") (pinfunction "3_13") (pintype "passive"))
    )
    (net (code "59") (name "Net-(U5-4)") (class "Default")
      (node (ref "R18") (pin "2") (pinfunction "2_2") (pintype "passive"))
      (node (ref "SW_BLUE") (pin "2") (pinfunction "2_2") (pintype "passive"))
      (node (ref "U5") (pin "1") (pinfunction "4_1") (pintype "passive"))
    )
    (net (code "60") (name "Net-(U5-5)") (class "Default")
      (node (ref "R17") (pin "2") (pinfunction "2_2") (pintype "passive"))
      (node (ref "SW_YELLOW") (pin "2") (pinfunction "2_2") (pintype "passive"))
      (node (ref "U5") (pin "2") (pinfunction "5_2") (pintype "passive"))
    )
    (net (code "61") (name "Net-(U5-6)") (class "Default")
      (node (ref "R16") (pin "2") (pinfunction "2_2") (pintype "passive"))
      (node (ref "SW_GREEN") (pin "2") (pinfunction "2_2") (pintype "passive"))
      (node (ref "U5") (pin "3") (pinfunction "6_3") (pintype "passive"))
    )
    (net (code "62") (name "Net-(U5-7)") (class "Default")
      (node (ref "R15") (pin "2") (pinfunction "2_2") (pintype "passive"))
      (node (ref "SW_RED") (pin "2") (pinfunction "2_2") (pintype "passive"))
      (node (ref "U5") (pin "4") (pinfunction "7_4") (pintype "passive"))
    )
    (net (code "63") (name "VBAT") (class "Default")
      (node (ref "BT1") (pin "1") (pinfunction "+_1") (pintype "passive"))
      (node (ref "D1") (pin "1") (pinfunction "A_1") (pintype "passive"))
      (node (ref "J2") (pin "1") (pinfunction "1_1") (pintype "passive"))
    )
    (net (code "64") (name "VCC_3_3V") (class "Default")
      (node (ref "C18") (pin "2") (pinfunction "2_2") (pintype "passive"))
      (node (ref "C19") (pin "2") (pinfunction "2_2") (pintype "passive"))
      (node (ref "J2") (pin "14") (pinfunction "14_14") (pintype "passive"))
      (node (ref "U3") (pin "13") (pinfunction "3V3OUT_13") (pintype "power_in"))
    )
    (net (code "65") (name "VCC_5V") (class "Default")
      (node (ref "C13") (pin "1") (pinfunction "1_1") (pintype "passive"))
      (node (ref "C16") (pin "2") (pinfunction "2_2") (pintype "passive"))
      (node (ref "C17") (pin "2") (pinfunction "2_2") (pintype "passive"))
      (node (ref "C21") (pin "2") (pinfunction "2_2") (pintype "passive"))
      (node (ref "C25") (pin "2") (pinfunction "2_2") (pintype "passive"))
      (node (ref "C3") (pin "2") (pinfunction "2_2") (pintype "passive"))
      (node (ref "C4") (pin "2") (pinfunction "2_2") (pintype "passive"))
      (node (ref "C8") (pin "2") (pinfunction "2_2") (pintype "passive"))
      (node (ref "C9") (pin "2") (pinfunction "2_2") (pintype "passive"))
      (node (ref "D2") (pin "2") (pinfunction "K_2") (pintype "passive"))
      (node (ref "FB2") (pin "1") (pinfunction "1_1") (pintype "passive"))
      (node (ref "J2") (pin "4") (pinfunction "4_4") (pintype "passive"))
      (node (ref "J4") (pin "2") (pinfunction "2_2") (pintype "passive"))
      (node (ref "R1") (pin "1") (pinfunction "1_1") (pintype "passive"))
      (node (ref "R15") (pin "1") (pinfunction "1_1") (pintype "passive"))
      (node (ref "R16") (pin "1") (pinfunction "1_1") (pintype "passive"))
      (node (ref "R17") (pin "1") (pinfunction "1_1") (pintype "passive"))
      (node (ref "R18") (pin "1") (pinfunction "1_1") (pintype "passive"))
      (node (ref "R19") (pin "1") (pinfunction "1_1") (pintype "passive"))
      (node (ref "R2") (pin "2") (pinfunction "2_2") (pintype "passive"))
      (node (ref "R20") (pin "1") (pinfunction "1_1") (pintype "passive"))
      (node (ref "R21") (pin "1") (pinfunction "1_1") (pintype "passive"))
      (node (ref "R22") (pin "1") (pinfunction "1_1") (pintype "passive"))
      (node (ref "R23") (pin "1") (pinfunction "1_1") (pintype "passive"))
      (node (ref "R7") (pin "1") (pinfunction "1_1") (pintype "passive"))
      (node (ref "R8") (pin "1") (pinfunction "1_1") (pintype "passive"))
      (node (ref "TP_5V") (pin "1") (pinfunction "1_1") (pintype "passive"))
      (node (ref "U1") (pin "4") (pinfunction "VCC_4") (pintype "power_in"))
      (node (ref "U1") (pin "6") (pinfunction "VCC_6") (pintype "power_in"))
      (node (ref "U2") (pin "5") (pinfunction "OUT_5") (pintype "passive"))
      (node (ref "U3") (pin "14") (pinfunction "~{RESET}_14") (pintype "input"))
      (node (ref "U3") (pin "15") (pinfunction "VCC_15") (pintype "power_in"))
      (node (ref "U3") (pin "3") (pinfunction "VCCIO_3") (pintype "power_in"))
      (node (ref "U4") (pin "1") (pinfunction "SDB_1") (pintype "input"))
      (node (ref "U4") (pin "6") (pinfunction "Vcc_6") (pintype "power_in"))
      (node (ref "U5") (pin "16") (pinfunction "VCC_16") (pintype "power_in"))
    )
    (net (code "66") (name "VCC_USB") (class "Default")
      (node (ref "C14") (pin "2") (pinfunction "2_2") (pintype "passive"))
      (node (ref "C15") (pin "2") (pinfunction "2_2") (pintype "passive"))
      (node (ref "D2") (pin "1") (pinfunction "A_1") (pintype "passive"))
      (node (ref "FB1") (pin "1") (pinfunction "1_1") (pintype "passive"))
    )
    (net (code "67") (name "VIN") (class "Default")
      (node (ref "D1") (pin "2") (pinfunction "K_2") (pintype "passive"))
      (node (ref "SW_ON") (pin "2") (pinfunction "COM_2") (pintype "passive"))
    )
    (net (code "68") (name "VIN_SW") (class "Default")
      (node (ref "C1") (pin "2") (pinfunction "2_2") (pintype "passive"))
      (node (ref "SW_ON") (pin "1") (pinfunction "1_1") (pintype "passive"))
      (node (ref "U2") (pin "1") (pinfunction "IN_1") (pintype "passive"))
      (node (ref "U2") (pin "3") (pinfunction "EN_3") (pintype "passive"))
    )
    (net (code "69") (name "unconnected-(J3-ID-Pad4)") (class "Default")
      (node (ref "J3") (pin "4") (pinfunction "ID_4") (pintype "passive"))
    )
    (net (code "70") (name "unconnected-(SW_MODE-Pad3)") (class "Default")
      (node (ref "SW_MODE") (pin "3") (pinfunction "3_3") (pintype "passive"))
    )
    (net (code "71") (name "unconnected-(SW_ON-Pad3)") (class "Default")
      (node (ref "SW_ON") (pin "3") (pinfunction "3_3") (pintype "passive"))
    )
    (net (code "72") (name "unconnected-(U3-CBUS0-Pad18)") (class "Default")
      (node (ref "U3") (pin "18") (pinfunction "CBUS0_18") (pintype "bidirectional"))
    )
    (net (code "73") (name "unconnected-(U3-CBUS3-Pad19)") (class "Default")
      (node (ref "U3") (pin "19") (pinfunction "CBUS3_19") (pintype "bidirectional"))
    )
    (net (code "74") (name "unconnected-(U3-~{CTS}-Pad9)") (class "Default")
      (node (ref "U3") (pin "9") (pinfunction "~{CTS}_9") (pintype "input"))
    )
    (net (code "75") (name "unconnected-(U3-~{DCD}-Pad8)") (class "Default")
      (node (ref "U3") (pin "8") (pinfunction "~{DCD}_8") (pintype "input"))
    )
    (net (code "76") (name "unconnected-(U3-~{DSR}-Pad7)") (class "Default")
      (node (ref "U3") (pin "7") (pinfunction "~{DSR}_7") (pintype "input"))
    )
    (net (code "77") (name "unconnected-(U3-~{RI}-Pad5)") (class "Default")
      (node (ref "U3") (pin "5") (pinfunction "~{RI}_5") (pintype "input"))
    )
    (net (code "78") (name "unconnected-(U3-~{RTS}-Pad2)") (class "Default")
      (node (ref "U3") (pin "2") (pinfunction "~{RTS}_2") (pintype "output"))
    )
    (net (code "79") (name "unconnected-(U5-EO-Pad15)") (class "Default")
      (node (ref "U5") (pin "15") (pinfunction "EO_15") (pintype "passive"))
    )
    (net (code "80") (name "unconnected-(U5-GS-Pad14)") (class "Default")
      (node (ref "U5") (pin "14") (pinfunction "GS_14") (pintype "passive"))
    )
  )
)
